# rooftop_reflector_v1_3.net
KiCad netlist of a schematic drawn in EAGLE
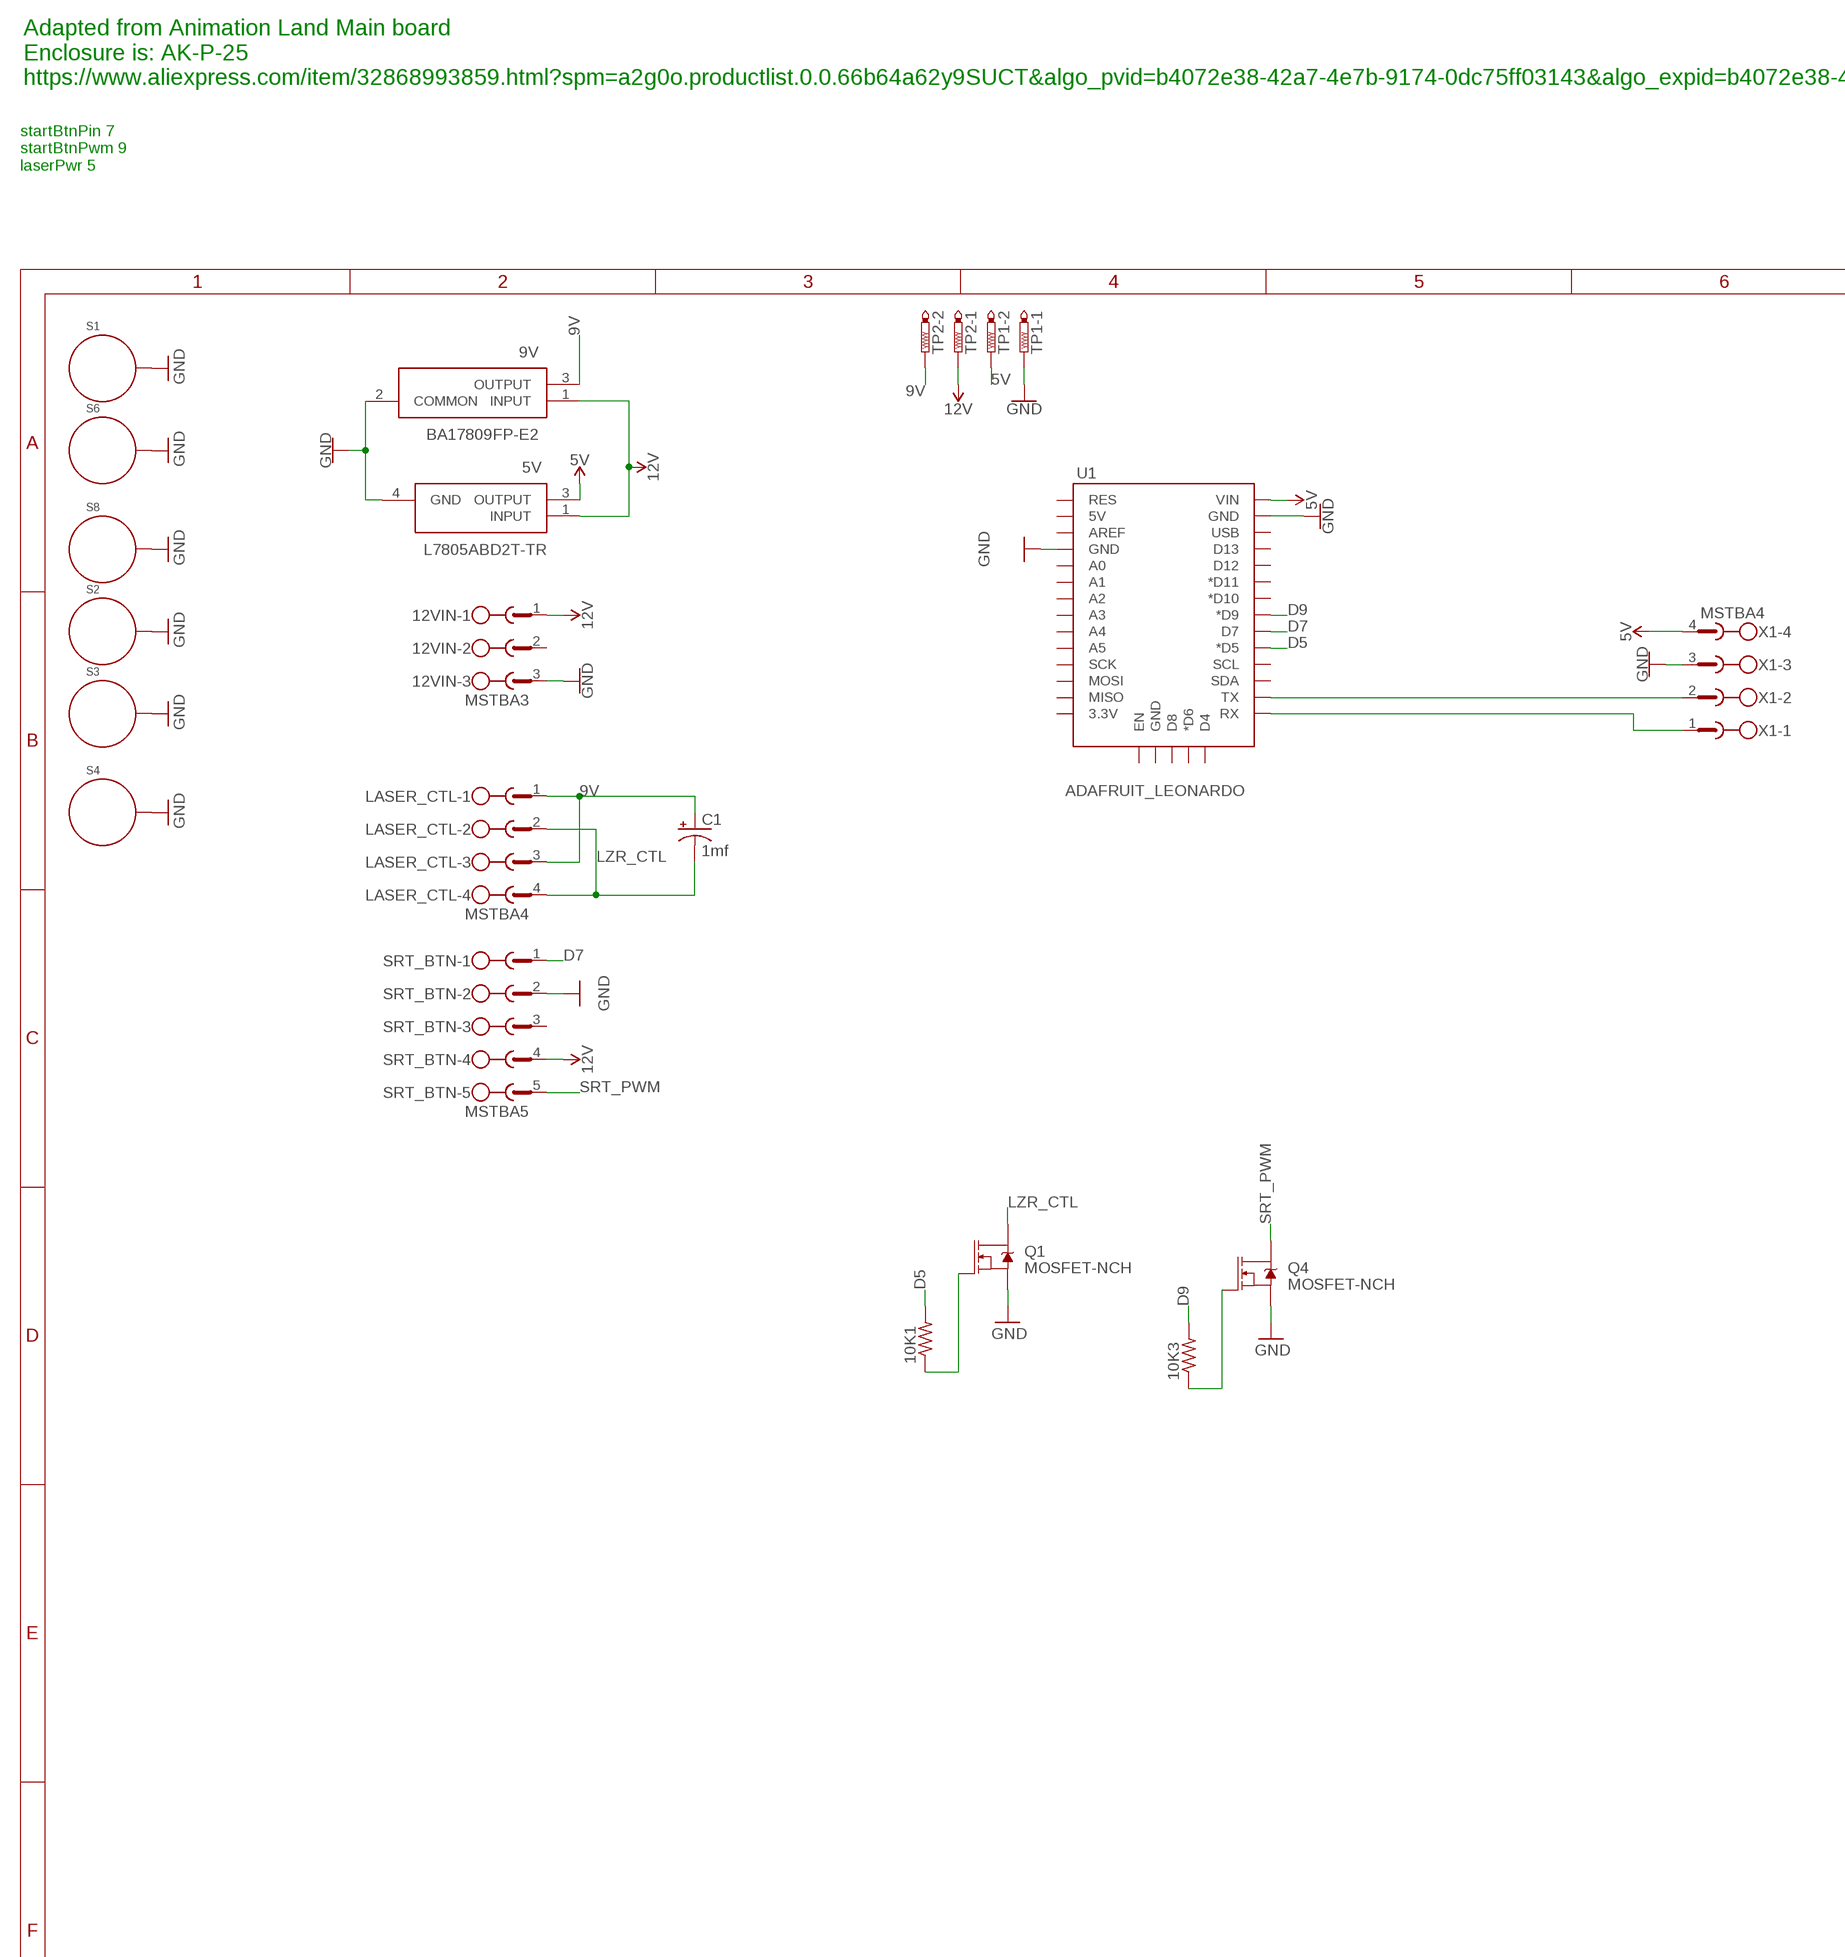
[diagram p0: schematic, sheet 1, part 1 of 2]
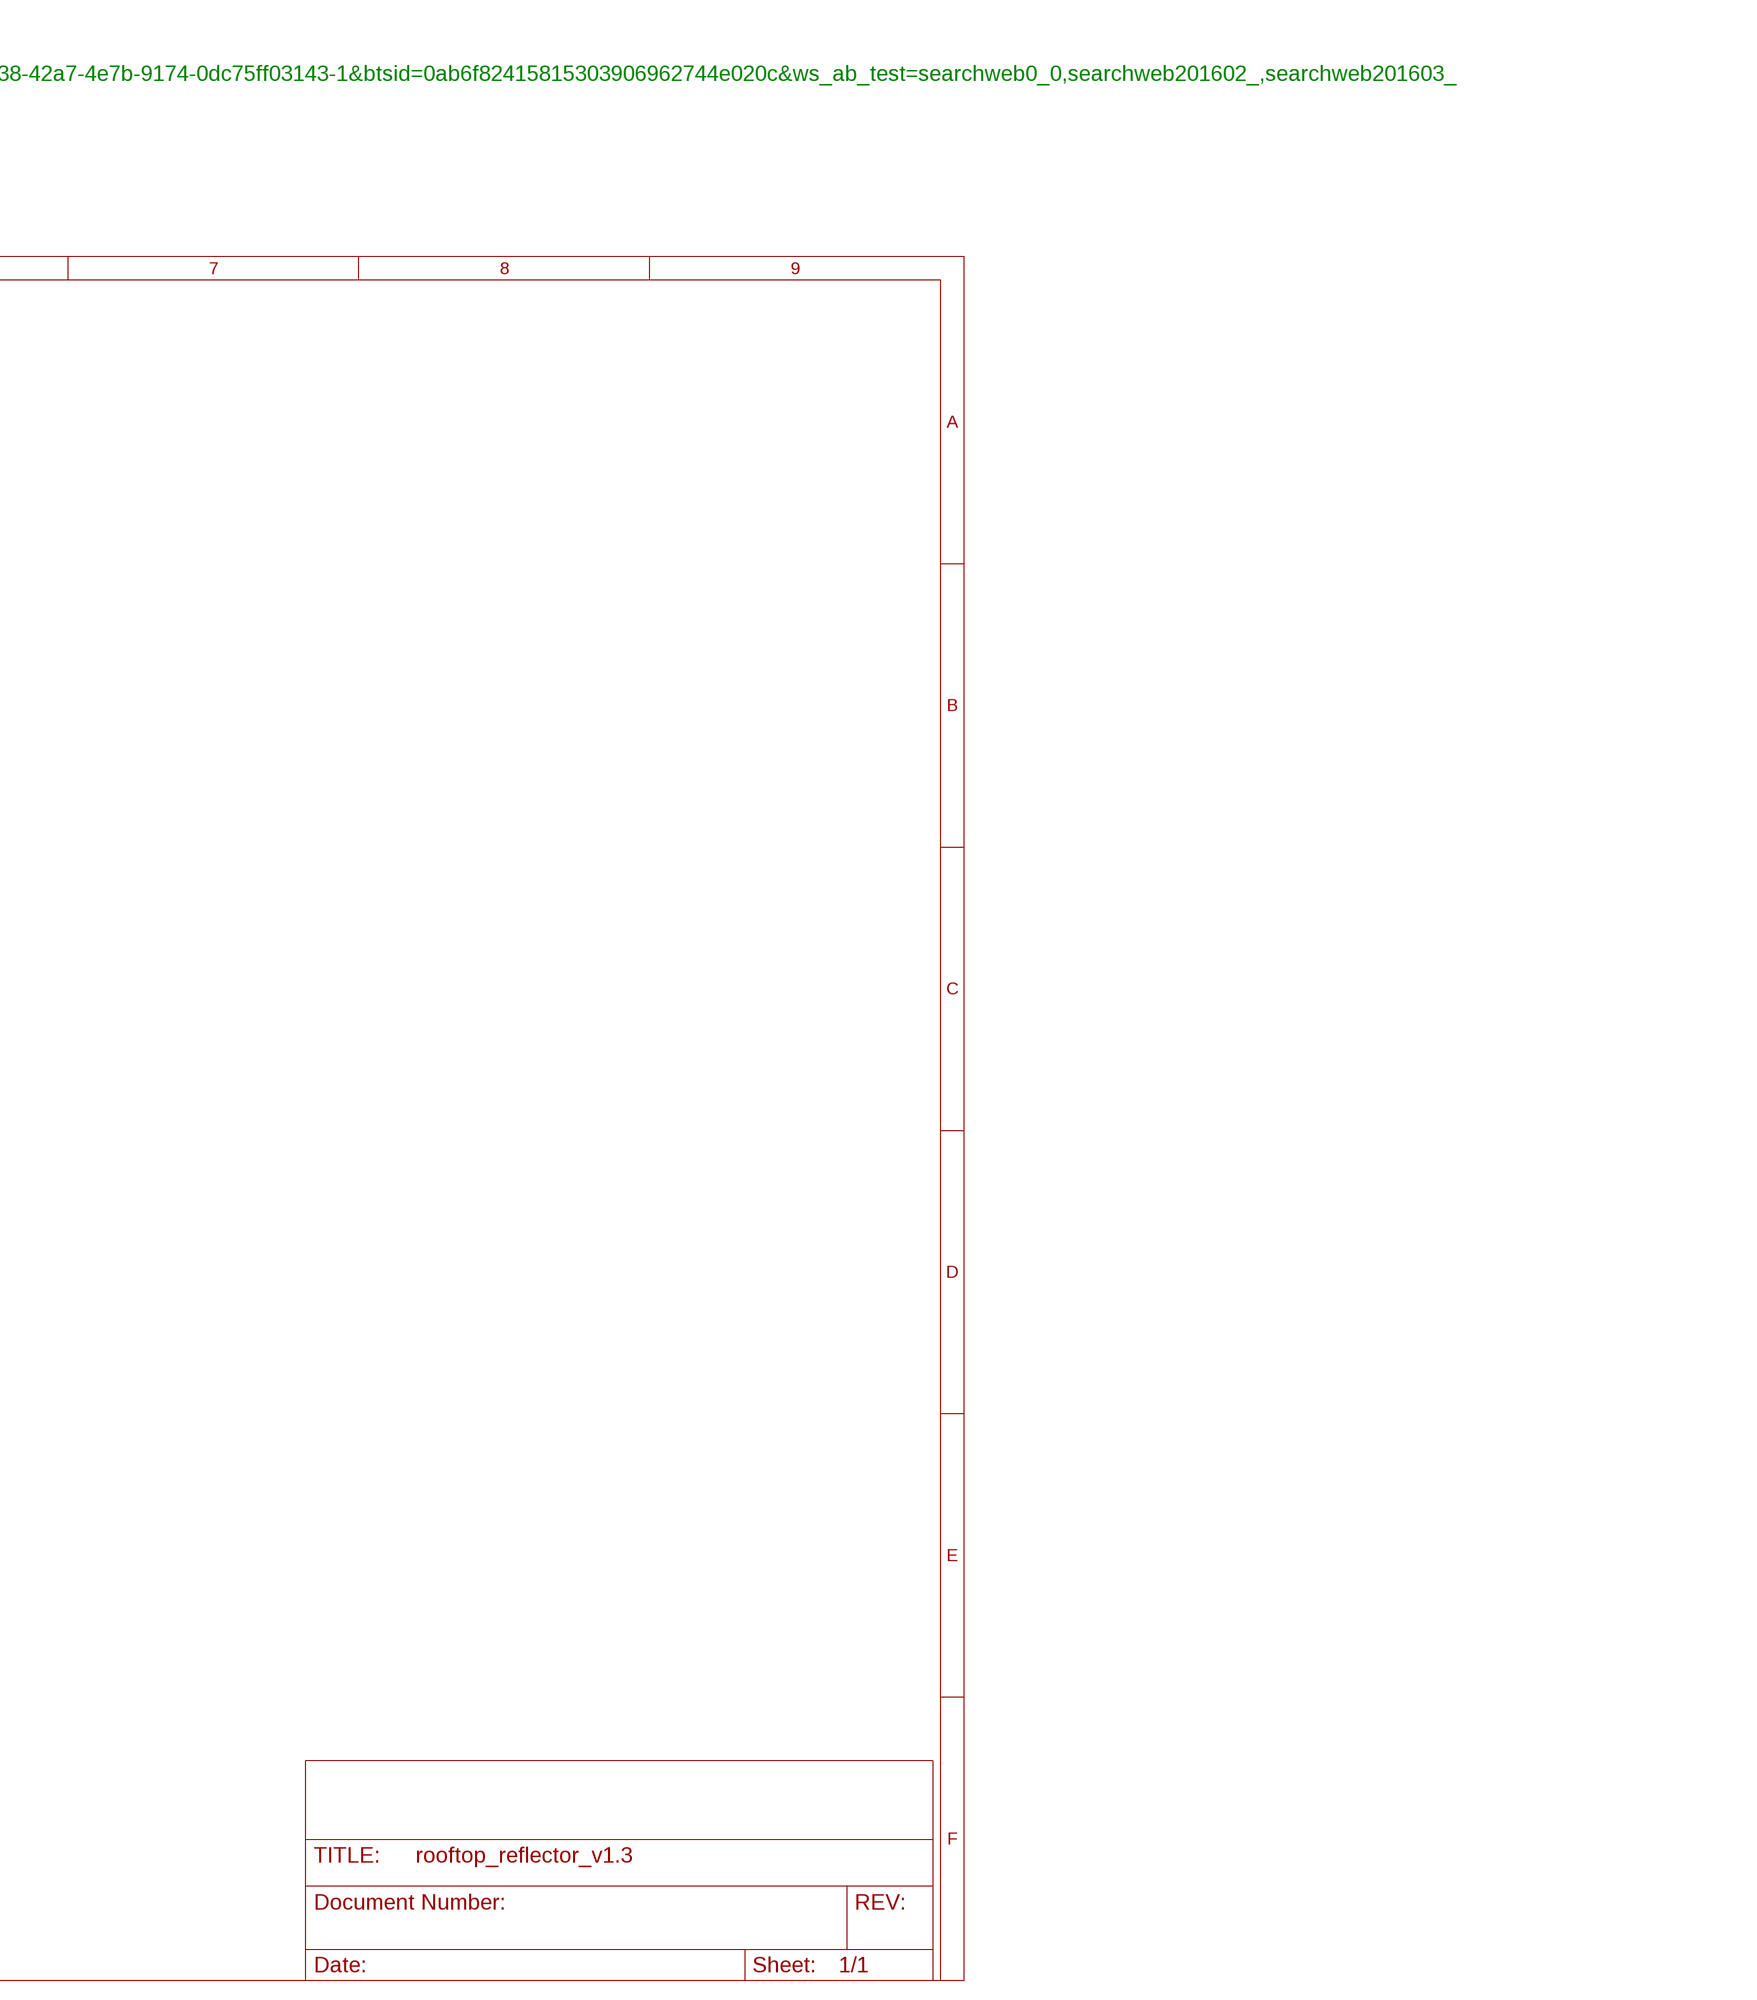
[diagram p1: schematic, sheet 1, part 2 of 2]

(export (version "E")
  (design (tool "Eeschema 10.0.6"))
  (components
    (comp (ref "5V")
      (value "L7805ABD2T-TR")
      (footprint "eagle-import:D2PAK-STB35NF10T4")
      (fields (field (name "MOUSER_PART_NUMBER") "511-L7805ABD2T-TR"))
      (libsource (lib "eagle-import") (part "L7805ABD2T-TR"))
    )
    (comp (ref "9V")
      (value "BA17809FP-E2")
      (footprint "eagle-import:BA17809FPE2")
      (fields (field (name "MOUSER_PART_NUMBER") "755-BA17809FP-E2"))
      (libsource (lib "eagle-import") (part "BA17809FP-E2"))
    )
    (comp (ref "10K1")
      (value "R-US_M0805")
      (footprint "eagle-import:M0805")
      (libsource (lib "eagle-import") (part "R-US_M0805"))
    )
    (comp (ref "10K3")
      (value "R-US_M0805")
      (footprint "eagle-import:M0805")
      (libsource (lib "eagle-import") (part "R-US_M0805"))
    )
    (comp (ref "12VIN")
      (value "MSTBA3")
      (footprint "eagle-import:MSTBA3")
      (fields (field (name "MF") "FARNELL") (field (name "MPN") "1757255"))
      (libsource (lib "eagle-import") (part "MSTBA3"))
    )
    (comp (ref "C1")
      (value "1mf")
      (footprint "eagle-import:CAP_RADIAL_10MM")
      (libsource (lib "eagle-import") (part "CAP_RADIAL_10MM-RADIAL-5MM-25V-20%"))
    )
    (comp (ref "LASER_CTL")
      (value "MSTBA4")
      (footprint "eagle-import:MSTBA4")
      (fields (field (name "MF") "FARNELL") (field (name "MPN") "1757268"))
      (libsource (lib "eagle-import") (part "MSTBA4"))
    )
    (comp (ref "Q1")
      (value "MOSFET-NCH")
      (footprint "eagle-import:SO-8_POWER_PAK")
      (libsource (lib "eagle-import") (part "MOSFET-NCH"))
    )
    (comp (ref "Q4")
      (value "MOSFET-NCH")
      (footprint "eagle-import:SO-8_POWER_PAK")
      (libsource (lib "eagle-import") (part "MOSFET-NCH"))
    )
    (comp (ref "S1")
      (value "STANDOFF_ELECTRICAL5-32")
      (footprint "eagle-import:STANDOFF_ELECTRICAL_5_32")
      (libsource (lib "eagle-import") (part "STANDOFF_ELECTRICAL5-32"))
    )
    (comp (ref "S2")
      (value "STANDOFF_ELECTRICAL5-32")
      (footprint "eagle-import:STANDOFF_ELECTRICAL_5_32")
      (libsource (lib "eagle-import") (part "STANDOFF_ELECTRICAL5-32"))
    )
    (comp (ref "S3")
      (value "STANDOFF_ELECTRICAL5-32")
      (footprint "eagle-import:STANDOFF_ELECTRICAL_5_32")
      (libsource (lib "eagle-import") (part "STANDOFF_ELECTRICAL5-32"))
    )
    (comp (ref "S4")
      (value "STANDOFF_ELECTRICAL5-32")
      (footprint "eagle-import:STANDOFF_ELECTRICAL_5_32")
      (libsource (lib "eagle-import") (part "STANDOFF_ELECTRICAL5-32"))
    )
    (comp (ref "S6")
      (value "STANDOFF_ELECTRICAL5-32")
      (footprint "eagle-import:STANDOFF_ELECTRICAL_5_32")
      (libsource (lib "eagle-import") (part "STANDOFF_ELECTRICAL5-32"))
    )
    (comp (ref "S8")
      (value "STANDOFF_ELECTRICAL5-32")
      (footprint "eagle-import:STANDOFF_ELECTRICAL_5_32")
      (libsource (lib "eagle-import") (part "STANDOFF_ELECTRICAL5-32"))
    )
    (comp (ref "SRT_BTN")
      (value "MSTBA5")
      (footprint "eagle-import:MSTBA5")
      (fields (field (name "MPN") "1757271"))
      (libsource (lib "eagle-import") (part "MSTBA5"))
    )
    (comp (ref "TP1")
      (value "PTR2")
      (footprint "eagle-import:P2-38-17")
      (libsource (lib "eagle-import") (part "PTR2"))
    )
    (comp (ref "TP2")
      (value "PTR2")
      (footprint "eagle-import:P2-38-17")
      (libsource (lib "eagle-import") (part "PTR2"))
    )
    (comp (ref "U1")
      (value "ADAFRUIT_LEONARDO")
      (footprint "eagle-import:ADAFRUIT_LENOARDO")
      (libsource (lib "eagle-import") (part "ADAFRUIT_LEONARDO"))
    )
    (comp (ref "X1")
      (value "MSTBA4")
      (footprint "eagle-import:MSTBA4")
      (fields (field (name "MF") "FARNELL") (field (name "MPN") "1757268"))
      (libsource (lib "eagle-import") (part "MSTBA4"))
    )
  )
  (nets
    (net (code "1") (name "/9V") (class "Default")
      (node (ref "9V") (pin "3") (pinfunction "OUTPUT_3") (pintype "bidirectional"))
      (node (ref "C1") (pin "+") (pinfunction "+_+") (pintype "passive"))
      (node (ref "LASER_CTL") (pin "1") (pinfunction "1_1") (pintype "passive"))
      (node (ref "LASER_CTL") (pin "3") (pinfunction "1_3") (pintype "passive"))
      (node (ref "TP2") (pin "TP-2") (pinfunction "TP_TP-2") (pintype "input"))
    )
    (net (code "2") (name "/D5") (class "Default")
      (node (ref "10K1") (pin "2") (pinfunction "2_2") (pintype "passive"))
      (node (ref "U1") (pin "D5") (pinfunction "*D5_D5") (pintype "bidirectional"))
    )
    (net (code "3") (name "/D7") (class "Default")
      (node (ref "SRT_BTN") (pin "1") (pinfunction "1_1") (pintype "passive"))
      (node (ref "U1") (pin "D7") (pinfunction "D7_D7") (pintype "bidirectional"))
    )
    (net (code "4") (name "/D9") (class "Default")
      (node (ref "10K3") (pin "2") (pinfunction "2_2") (pintype "passive"))
      (node (ref "U1") (pin "D9") (pinfunction "*D9_D9") (pintype "bidirectional"))
    )
    (net (code "5") (name "/LZR_CTL") (class "Default")
      (node (ref "C1") (pin "-") (pinfunction "-_-") (pintype "passive"))
      (node (ref "LASER_CTL") (pin "2") (pinfunction "1_2") (pintype "passive"))
      (node (ref "LASER_CTL") (pin "4") (pinfunction "1_4") (pintype "passive"))
      (node (ref "Q1") (pin "D1") (pinfunction "D_D1") (pintype "bidirectional"))
    )
    (net (code "6") (name "/SRT_PWM") (class "Default")
      (node (ref "Q4") (pin "D1") (pinfunction "D_D1") (pintype "bidirectional"))
      (node (ref "SRT_BTN") (pin "5") (pinfunction "1_5") (pintype "passive"))
    )
    (net (code "7") (name "5V") (class "Default")
      (node (ref "5V") (pin "3") (pinfunction "OUTPUT_3") (pintype "bidirectional"))
      (node (ref "TP1") (pin "TP-2") (pinfunction "TP_TP-2") (pintype "input"))
      (node (ref "U1") (pin "VIN") (pinfunction "VIN_VIN") (pintype "bidirectional"))
      (node (ref "X1") (pin "4") (pinfunction "1_4") (pintype "passive"))
    )
    (net (code "8") (name "12V") (class "Default")
      (node (ref "12VIN") (pin "1") (pinfunction "1_1") (pintype "passive"))
      (node (ref "5V") (pin "1") (pinfunction "INPUT_1") (pintype "bidirectional"))
      (node (ref "9V") (pin "1") (pinfunction "INPUT_1") (pintype "bidirectional"))
      (node (ref "SRT_BTN") (pin "4") (pinfunction "1_4") (pintype "passive"))
      (node (ref "TP2") (pin "TP-1") (pinfunction "TP_TP-1") (pintype "input"))
    )
    (net (code "9") (name "GND") (class "Default")
      (node (ref "12VIN") (pin "3") (pinfunction "1_3") (pintype "passive"))
      (node (ref "5V") (pin "4") (pinfunction "GND_4") (pintype "bidirectional"))
      (node (ref "9V") (pin "2") (pinfunction "COMMON_2") (pintype "bidirectional"))
      (node (ref "Q1") (pin "S") (pinfunction "S_S") (pintype "bidirectional"))
      (node (ref "Q4") (pin "S") (pinfunction "S_S") (pintype "bidirectional"))
      (node (ref "S1") (pin "P1") (pinfunction "P$1_P1") (pintype "bidirectional"))
      (node (ref "S2") (pin "P1") (pinfunction "P$1_P1") (pintype "bidirectional"))
      (node (ref "S3") (pin "P1") (pinfunction "P$1_P1") (pintype "bidirectional"))
      (node (ref "S4") (pin "P1") (pinfunction "P$1_P1") (pintype "bidirectional"))
      (node (ref "S6") (pin "P1") (pinfunction "P$1_P1") (pintype "bidirectional"))
      (node (ref "S8") (pin "P1") (pinfunction "P$1_P1") (pintype "bidirectional"))
      (node (ref "SRT_BTN") (pin "2") (pinfunction "1_2") (pintype "passive"))
      (node (ref "TP1") (pin "TP-1") (pinfunction "TP_TP-1") (pintype "input"))
      (node (ref "U1") (pin "GND@0") (pinfunction "GND_GND@0") (pintype "bidirectional"))
      (node (ref "U1") (pin "GND@2") (pinfunction "GND_GND@2") (pintype "bidirectional"))
      (node (ref "X1") (pin "3") (pinfunction "1_3") (pintype "passive"))
    )
    (net (code "10") (name "Net-(10K1-Pad1)") (class "Default")
      (node (ref "10K1") (pin "1") (pinfunction "1_1") (pintype "passive"))
      (node (ref "Q1") (pin "G") (pinfunction "G_G") (pintype "bidirectional"))
    )
    (net (code "11") (name "Net-(10K3-Pad1)") (class "Default")
      (node (ref "10K3") (pin "1") (pinfunction "1_1") (pintype "passive"))
      (node (ref "Q4") (pin "G") (pinfunction "G_G") (pintype "bidirectional"))
    )
    (net (code "12") (name "Net-(U1-PadRX)") (class "Default")
      (node (ref "U1") (pin "RX") (pinfunction "RX_RX") (pintype "bidirectional"))
      (node (ref "X1") (pin "1") (pinfunction "1_1") (pintype "passive"))
    )
    (net (code "13") (name "Net-(X1B-1)") (class "Default")
      (node (ref "U1") (pin "TX") (pinfunction "TX_TX") (pintype "bidirectional"))
      (node (ref "X1") (pin "2") (pinfunction "1_2") (pintype "passive"))
    )
    (net (code "14") (name "unconnected-(12VINB-1-Pad2)") (class "Default")
      (node (ref "12VIN") (pin "2") (pinfunction "1_2") (pintype "passive"))
    )
    (net (code "15") (name "unconnected-(SRT_BTNC-1-Pad3)") (class "Default")
      (node (ref "SRT_BTN") (pin "3") (pinfunction "1_3") (pintype "passive"))
    )
    (net (code "16") (name "unconnected-(U1-*D6-PadD6)") (class "Default")
      (node (ref "U1") (pin "D6") (pinfunction "*D6_D6") (pintype "bidirectional"))
    )
    (net (code "17") (name "unconnected-(U1-*D10-PadD10)") (class "Default")
      (node (ref "U1") (pin "D10") (pinfunction "*D10_D10") (pintype "bidirectional"))
    )
    (net (code "18") (name "unconnected-(U1-*D11-PadD11)") (class "Default")
      (node (ref "U1") (pin "D11") (pinfunction "*D11_D11") (pintype "bidirectional"))
    )
    (net (code "19") (name "unconnected-(U1-3.3V-Pad3V)") (class "Default")
      (node (ref "U1") (pin "3V") (pinfunction "3.3V_3V") (pintype "bidirectional"))
    )
    (net (code "20") (name "unconnected-(U1-GND-PadGND@1)") (class "Default")
      (node (ref "U1") (pin "GND@1") (pinfunction "GND_GND@1") (pintype "bidirectional"))
    )
    (net (code "21") (name "unconnected-(U1-Pad5V)") (class "Default")
      (node (ref "U1") (pin "5V") (pinfunction "5V_5V") (pintype "bidirectional"))
    )
    (net (code "22") (name "unconnected-(U1-PadA0)") (class "Default")
      (node (ref "U1") (pin "A0") (pinfunction "A0_A0") (pintype "bidirectional"))
    )
    (net (code "23") (name "unconnected-(U1-PadA1)") (class "Default")
      (node (ref "U1") (pin "A1") (pinfunction "A1_A1") (pintype "bidirectional"))
    )
    (net (code "24") (name "unconnected-(U1-PadA2)") (class "Default")
      (node (ref "U1") (pin "A2") (pinfunction "A2_A2") (pintype "bidirectional"))
    )
    (net (code "25") (name "unconnected-(U1-PadA3)") (class "Default")
      (node (ref "U1") (pin "A3") (pinfunction "A3_A3") (pintype "bidirectional"))
    )
    (net (code "26") (name "unconnected-(U1-PadA4)") (class "Default")
      (node (ref "U1") (pin "A4") (pinfunction "A4_A4") (pintype "bidirectional"))
    )
    (net (code "27") (name "unconnected-(U1-PadA5)") (class "Default")
      (node (ref "U1") (pin "A5") (pinfunction "A5_A5") (pintype "bidirectional"))
    )
    (net (code "28") (name "unconnected-(U1-PadAREF)") (class "Default")
      (node (ref "U1") (pin "AREF") (pinfunction "AREF_AREF") (pintype "bidirectional"))
    )
    (net (code "29") (name "unconnected-(U1-PadD4)") (class "Default")
      (node (ref "U1") (pin "D4") (pinfunction "D4_D4") (pintype "bidirectional"))
    )
    (net (code "30") (name "unconnected-(U1-PadD8)") (class "Default")
      (node (ref "U1") (pin "D8") (pinfunction "D8_D8") (pintype "bidirectional"))
    )
    (net (code "31") (name "unconnected-(U1-PadD12)") (class "Default")
      (node (ref "U1") (pin "D12") (pinfunction "D12_D12") (pintype "bidirectional"))
    )
    (net (code "32") (name "unconnected-(U1-PadD13)") (class "Default")
      (node (ref "U1") (pin "D13") (pinfunction "D13_D13") (pintype "bidirectional"))
    )
    (net (code "33") (name "unconnected-(U1-PadEN)") (class "Default")
      (node (ref "U1") (pin "EN") (pinfunction "EN_EN") (pintype "bidirectional"))
    )
    (net (code "34") (name "unconnected-(U1-PadMISO)") (class "Default")
      (node (ref "U1") (pin "MISO") (pinfunction "MISO_MISO") (pintype "bidirectional"))
    )
    (net (code "35") (name "unconnected-(U1-PadMOSI)") (class "Default")
      (node (ref "U1") (pin "MOSI") (pinfunction "MOSI_MOSI") (pintype "bidirectional"))
    )
    (net (code "36") (name "unconnected-(U1-PadRES)") (class "Default")
      (node (ref "U1") (pin "RES") (pinfunction "RES_RES") (pintype "bidirectional"))
    )
    (net (code "37") (name "unconnected-(U1-PadSCK)") (class "Default")
      (node (ref "U1") (pin "SCK") (pinfunction "SCK_SCK") (pintype "bidirectional"))
    )
    (net (code "38") (name "unconnected-(U1-PadSCL)") (class "Default")
      (node (ref "U1") (pin "SCL") (pinfunction "SCL_SCL") (pintype "bidirectional"))
    )
    (net (code "39") (name "unconnected-(U1-PadSDA)") (class "Default")
      (node (ref "U1") (pin "SDA") (pinfunction "SDA_SDA") (pintype "bidirectional"))
    )
    (net (code "40") (name "unconnected-(U1-PadUSB)") (class "Default")
      (node (ref "U1") (pin "USB") (pinfunction "USB_USB") (pintype "bidirectional"))
    )
  )
)
